# Resonator_filter_design.net
KiCad netlist of a schematic drawn in Altium Designer
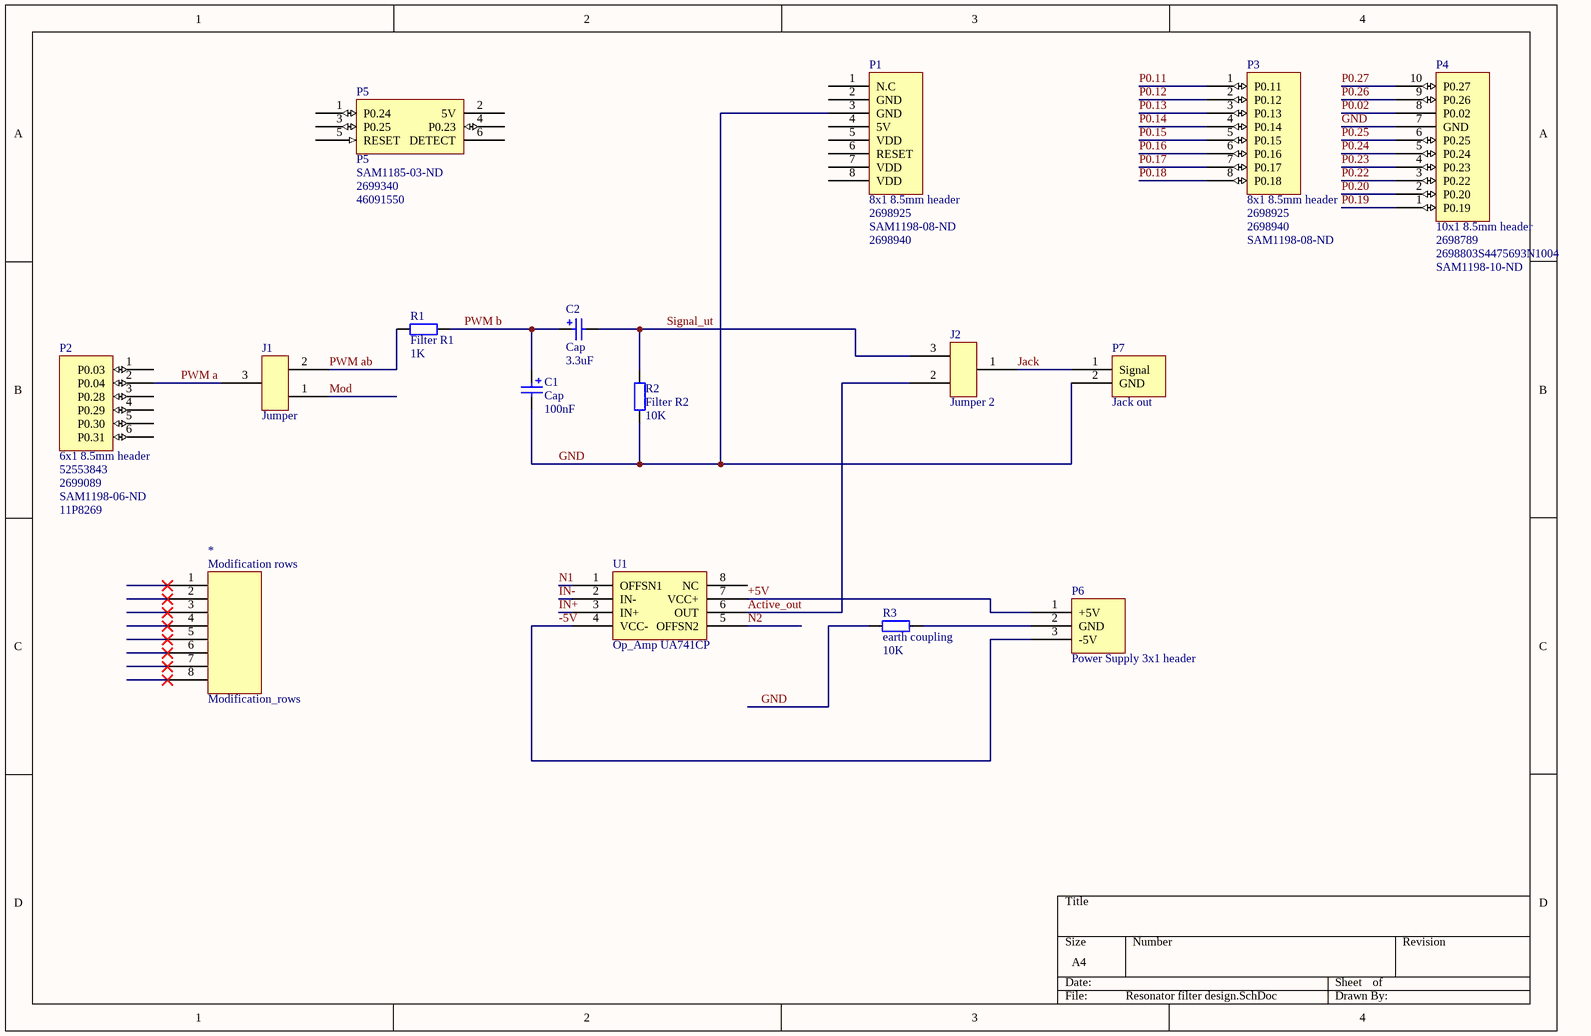
[diagram p0: Resonator filter design.SchDoc]

(export (version "E")
  (design (tool "Eeschema 10.0.6"))
  (components
    (comp (ref "*")
      (value "Modification_rows")
      (libsource (lib "Resonator filter design") (part "Modification_rows"))
    )
    (comp (ref "C1")
      (value "Cap")
      (footprint "Cap 100nF")
      (description "Polarized Capacitor (Axial)")
      (fields (field (name "ALTIUM_VALUE") "100nF") (field (name "PUBLISHER") "Altium Limited"))
      (libsource (lib "Miscellaneous Devices") (part "Cap Pol2"))
    )
    (comp (ref "C2")
      (value "Cap")
      (footprint "Cap 3.3uF")
      (description "Polarized Capacitor (Axial)")
      (fields (field (name "ALTIUM_VALUE") "3.3uF") (field (name "PUBLISHER") "Altium Limited"))
      (libsource (lib "Miscellaneous Devices") (part "Cap Pol2"))
    )
    (comp (ref "J1")
      (value "Jumper")
      (footprint "Jumper")
      (libsource (lib "Resonator filter design") (part "Jumper"))
    )
    (comp (ref "J2")
      (value "Jumper 2")
      (footprint "Jumper2")
      (libsource (lib "Resonator filter design") (part "Jumper 2"))
    )
    (comp (ref "P1")
      (value "8x1 8.5mm header")
      (footprint "Header 8x1 8.5mm")
      (fields
        (field (name "SUPPLIER PART NUMBER 1") "2698925")
        (field (name "SUPPLIER PART NUMBER 2") "SAM1198-08-ND")
        (field (name "SUPPLIER PART NUMBER 3") "2698940")
      )
      (libsource (lib "Resonator filter design") (part "POWER P1"))
    )
    (comp (ref "P2")
      (value "6x1 8.5mm header")
      (footprint "Header 6x1 8.5mm")
      (fields
        (field (name "SUPPLIER PART NUMBER 1") "52553843")
        (field (name "SUPPLIER PART NUMBER 2") "2699089")
        (field (name "SUPPLIER PART NUMBER 3") "SAM1198-06-ND")
        (field (name "SUPPLIER PART NUMBER 4") "11P8269")
      )
      (libsource (lib "Resonator filter design") (part "P2"))
    )
    (comp (ref "P3")
      (value "8x1 8.5mm header")
      (footprint "Header 8x1 8.5mm")
      (fields
        (field (name "SUPPLIER PART NUMBER 1") "2698925")
        (field (name "SUPPLIER PART NUMBER 2") "2698940")
        (field (name "SUPPLIER PART NUMBER 3") "SAM1198-08-ND")
      )
      (libsource (lib "Resonator filter design") (part "P3"))
    )
    (comp (ref "P4")
      (value "10x1 8.5mm header")
      (footprint "Header 10x1 8.5mm")
      (fields
        (field (name "SUPPLIER PART NUMBER 1") "2698789")
        (field (name "SUPPLIER PART NUMBER 2") "2698803S4475693N1004")
        (field (name "SUPPLIER PART NUMBER 3") "SAM1198-10-ND")
      )
      (libsource (lib "Resonator filter design") (part "P4"))
    )
    (comp (ref "P5")
      (value "P5")
      (footprint "ICSP")
      (fields
        (field (name "SUPPLIER PART NUMBER 1") "SAM1185-03-ND")
        (field (name "SUPPLIER PART NUMBER 2") "2699340")
        (field (name "SUPPLIER PART NUMBER 3") "46091550")
      )
      (libsource (lib "Resonator filter design") (part "P5"))
    )
    (comp (ref "P6")
      (value "Power Supply 3x1 header")
      (footprint "Power Supply connector")
      (libsource (lib "Resonator filter design") (part "Power Supply"))
    )
    (comp (ref "P7")
      (value "Jack out")
      (footprint "Jack out")
      (libsource (lib "Resonator filter design") (part "Jack out"))
    )
    (comp (ref "R1")
      (value "Filter R1")
      (footprint "AXIAL-0.4")
      (description "Resistor")
      (fields (field (name "ALTIUM_VALUE") "1K") (field (name "PUBLISHER") "Altium Limited"))
      (libsource (lib "") (part "Res2_2"))
    )
    (comp (ref "R2")
      (value "Filter R2")
      (footprint "AXIAL-0.4")
      (description "Resistor")
      (fields (field (name "ALTIUM_VALUE") "10K") (field (name "PUBLISHER") "Altium Limited"))
      (libsource (lib "") (part "Res2_1"))
    )
    (comp (ref "R3")
      (value "earth coupling")
      (footprint "AXIAL-0.4")
      (description "Resistor")
      (fields (field (name "ALTIUM_VALUE") "10K") (field (name "PUBLISHER") "Altium Limited"))
      (libsource (lib "Miscellaneous Devices") (part "Res2"))
    )
    (comp (ref "U1")
      (value "Op_Amp UA741CP")
      (footprint "Op-Amp UA741CP")
      (libsource (lib "Resonator filter design") (part "Op_Amp UA741CP"))
    )
  )
  (nets
    (net (code "1") (name "/+5V") (class "Default")
      (node (ref "P6") (pin "1") (pinfunction "+5V_1") (pintype "passive"))
      (node (ref "U1") (pin "7") (pinfunction "VCC+_7") (pintype "passive"))
    )
    (net (code "2") (name "/-5V") (class "Default")
      (node (ref "P6") (pin "3") (pinfunction "-5V_3") (pintype "passive"))
      (node (ref "U1") (pin "4") (pinfunction "VCC-_4") (pintype "passive"))
    )
    (net (code "3") (name "/Active_out") (class "Default")
      (node (ref "J2") (pin "2") (pintype "passive"))
      (node (ref "U1") (pin "6") (pinfunction "OUT_6") (pintype "passive"))
    )
    (net (code "4") (name "/GND") (class "Default")
      (node (ref "C1") (pin "2") (pinfunction "2_2") (pintype "passive"))
      (node (ref "P1") (pin "3") (pinfunction "GND_3") (pintype "power_in"))
      (node (ref "P4") (pin "7") (pinfunction "GND_7") (pintype "power_in"))
      (node (ref "P7") (pin "2") (pinfunction "GND_2") (pintype "passive"))
      (node (ref "R2") (pin "1") (pinfunction "1_1") (pintype "passive"))
      (node (ref "R3") (pin "2") (pinfunction "2_2") (pintype "passive"))
    )
    (net (code "5") (name "/IN+") (class "Default")
      (node (ref "U1") (pin "3") (pinfunction "IN+_3") (pintype "passive"))
    )
    (net (code "6") (name "/IN-") (class "Default")
      (node (ref "U1") (pin "2") (pinfunction "IN-_2") (pintype "passive"))
    )
    (net (code "7") (name "/Jack") (class "Default")
      (node (ref "J2") (pin "1") (pintype "passive"))
      (node (ref "P7") (pin "1") (pinfunction "Signal_1") (pintype "passive"))
    )
    (net (code "8") (name "/Mod") (class "Default") (node (ref "J1") (pin "1") (pintype "passive")))
    (net (code "9") (name "/N1") (class "Default")
      (node (ref "U1") (pin "1") (pinfunction "OFFSN1_1") (pintype "passive"))
    )
    (net (code "10") (name "/N2") (class "Default")
      (node (ref "U1") (pin "5") (pinfunction "OFFSN2_5") (pintype "passive"))
    )
    (net (code "11") (name "/P0.02") (class "Default")
      (node (ref "P4") (pin "8") (pinfunction "P0.02_8") (pintype "passive"))
    )
    (net (code "12") (name "/P0.11") (class "Default")
      (node (ref "P3") (pin "1") (pinfunction "P0.11_1") (pintype "bidirectional"))
    )
    (net (code "13") (name "/P0.12") (class "Default")
      (node (ref "P3") (pin "2") (pinfunction "P0.12_2") (pintype "bidirectional"))
    )
    (net (code "14") (name "/P0.13") (class "Default")
      (node (ref "P3") (pin "3") (pinfunction "P0.13_3") (pintype "bidirectional"))
    )
    (net (code "15") (name "/P0.14") (class "Default")
      (node (ref "P3") (pin "4") (pinfunction "P0.14_4") (pintype "bidirectional"))
    )
    (net (code "16") (name "/P0.15") (class "Default")
      (node (ref "P3") (pin "5") (pinfunction "P0.15_5") (pintype "bidirectional"))
    )
    (net (code "17") (name "/P0.16") (class "Default")
      (node (ref "P3") (pin "6") (pinfunction "P0.16_6") (pintype "bidirectional"))
    )
    (net (code "18") (name "/P0.17") (class "Default")
      (node (ref "P3") (pin "7") (pinfunction "P0.17_7") (pintype "bidirectional"))
    )
    (net (code "19") (name "/P0.18") (class "Default")
      (node (ref "P3") (pin "8") (pinfunction "P0.18_8") (pintype "bidirectional"))
    )
    (net (code "20") (name "/P0.19") (class "Default")
      (node (ref "P4") (pin "1") (pinfunction "P0.19_1") (pintype "bidirectional"))
    )
    (net (code "21") (name "/P0.20") (class "Default")
      (node (ref "P4") (pin "2") (pinfunction "P0.20_2") (pintype "bidirectional"))
    )
    (net (code "22") (name "/P0.22") (class "Default")
      (node (ref "P4") (pin "3") (pinfunction "P0.22_3") (pintype "bidirectional"))
    )
    (net (code "23") (name "/P0.23") (class "Default")
      (node (ref "P4") (pin "4") (pinfunction "P0.23_4") (pintype "bidirectional"))
    )
    (net (code "24") (name "/P0.24") (class "Default")
      (node (ref "P4") (pin "5") (pinfunction "P0.24_5") (pintype "bidirectional"))
    )
    (net (code "25") (name "/P0.25") (class "Default")
      (node (ref "P4") (pin "6") (pinfunction "P0.25_6") (pintype "bidirectional"))
    )
    (net (code "26") (name "/P0.26") (class "Default")
      (node (ref "P4") (pin "9") (pinfunction "P0.26_9") (pintype "bidirectional"))
    )
    (net (code "27") (name "/P0.27") (class "Default")
      (node (ref "P4") (pin "10") (pinfunction "P0.27_10") (pintype "bidirectional"))
    )
    (net (code "28") (name "/PWM a") (class "Default")
      (node (ref "J1") (pin "3") (pintype "passive"))
      (node (ref "P2") (pin "2") (pinfunction "P0.04_2") (pintype "bidirectional"))
    )
    (net (code "29") (name "/PWM ab") (class "Default")
      (node (ref "J1") (pin "2") (pintype "passive"))
      (node (ref "R1") (pin "1") (pinfunction "1_1") (pintype "passive"))
    )
    (net (code "30") (name "/PWM b") (class "Default")
      (node (ref "C1") (pin "1") (pinfunction "1_1") (pintype "passive"))
      (node (ref "C2") (pin "1") (pinfunction "1_1") (pintype "passive"))
      (node (ref "R1") (pin "2") (pinfunction "2_2") (pintype "passive"))
    )
    (net (code "31") (name "/Signal_ut") (class "Default")
      (node (ref "C2") (pin "2") (pinfunction "2_2") (pintype "passive"))
      (node (ref "J2") (pin "3") (pintype "passive"))
      (node (ref "R2") (pin "2") (pinfunction "2_2") (pintype "passive"))
    )
    (net (code "32") (name "Net-(P6-GND)") (class "Default")
      (node (ref "P6") (pin "2") (pinfunction "GND_2") (pintype "passive"))
      (node (ref "R3") (pin "1") (pinfunction "1_1") (pintype "passive"))
    )
    (net (code "33") (name "unconnected-(*-Pad1)") (class "Default")
      (node (ref "*") (pin "1") (pintype "passive+no_connect"))
    )
    (net (code "34") (name "unconnected-(*-Pad2)") (class "Default")
      (node (ref "*") (pin "2") (pintype "passive+no_connect"))
    )
    (net (code "35") (name "unconnected-(*-Pad3)") (class "Default")
      (node (ref "*") (pin "3") (pintype "passive+no_connect"))
    )
    (net (code "36") (name "unconnected-(*-Pad4)") (class "Default")
      (node (ref "*") (pin "4") (pintype "passive+no_connect"))
    )
    (net (code "37") (name "unconnected-(*-Pad5)") (class "Default")
      (node (ref "*") (pin "5") (pintype "passive+no_connect"))
    )
    (net (code "38") (name "unconnected-(*-Pad6)") (class "Default")
      (node (ref "*") (pin "6") (pintype "passive+no_connect"))
    )
    (net (code "39") (name "unconnected-(*-Pad7)") (class "Default")
      (node (ref "*") (pin "7") (pintype "passive+no_connect"))
    )
    (net (code "40") (name "unconnected-(*-Pad8)") (class "Default")
      (node (ref "*") (pin "8") (pintype "passive+no_connect"))
    )
    (net (code "41") (name "unconnected-(P1-5V-Pad4)") (class "Default")
      (node (ref "P1") (pin "4") (pinfunction "5V_4") (pintype "power_in"))
    )
    (net (code "42") (name "unconnected-(P1-GND-Pad2)") (class "Default")
      (node (ref "P1") (pin "2") (pinfunction "GND_2") (pintype "power_in"))
    )
    (net (code "43") (name "unconnected-(P1-N.C-Pad1)") (class "Default")
      (node (ref "P1") (pin "1") (pinfunction "N.C_1") (pintype "power_in"))
    )
    (net (code "44") (name "unconnected-(P1-RESET-Pad6)") (class "Default")
      (node (ref "P1") (pin "6") (pinfunction "RESET_6") (pintype "passive"))
    )
    (net (code "45") (name "unconnected-(P1-VDD-Pad5)") (class "Default")
      (node (ref "P1") (pin "5") (pinfunction "VDD_5") (pintype "power_in"))
    )
    (net (code "46") (name "unconnected-(P1-VDD-Pad7)") (class "Default")
      (node (ref "P1") (pin "7") (pinfunction "VDD_7") (pintype "power_in"))
    )
    (net (code "47") (name "unconnected-(P1-VDD-Pad8)") (class "Default")
      (node (ref "P1") (pin "8") (pinfunction "VDD_8") (pintype "passive"))
    )
    (net (code "48") (name "unconnected-(P2-P0.03-Pad1)") (class "Default")
      (node (ref "P2") (pin "1") (pinfunction "P0.03_1") (pintype "bidirectional"))
    )
    (net (code "49") (name "unconnected-(P2-P0.28-Pad3)") (class "Default")
      (node (ref "P2") (pin "3") (pinfunction "P0.28_3") (pintype "bidirectional"))
    )
    (net (code "50") (name "unconnected-(P2-P0.29-Pad4)") (class "Default")
      (node (ref "P2") (pin "4") (pinfunction "P0.29_4") (pintype "bidirectional"))
    )
    (net (code "51") (name "unconnected-(P2-P0.30-Pad5)") (class "Default")
      (node (ref "P2") (pin "5") (pinfunction "P0.30_5") (pintype "bidirectional"))
    )
    (net (code "52") (name "unconnected-(P2-P0.31-Pad6)") (class "Default")
      (node (ref "P2") (pin "6") (pinfunction "P0.31_6") (pintype "bidirectional"))
    )
    (net (code "53") (name "unconnected-(P5-5V-Pad2)") (class "Default")
      (node (ref "P5") (pin "2") (pinfunction "5V_2") (pintype "power_in"))
    )
    (net (code "54") (name "unconnected-(P5-DETECT-Pad6)") (class "Default")
      (node (ref "P5") (pin "6") (pinfunction "DETECT_6") (pintype "power_in"))
    )
    (net (code "55") (name "unconnected-(P5-P0.23-Pad4)") (class "Default")
      (node (ref "P5") (pin "4") (pinfunction "P0.23_4") (pintype "bidirectional"))
    )
    (net (code "56") (name "unconnected-(P5-P0.24-Pad1)") (class "Default")
      (node (ref "P5") (pin "1") (pinfunction "P0.24_1") (pintype "bidirectional"))
    )
    (net (code "57") (name "unconnected-(P5-P0.25-Pad3)") (class "Default")
      (node (ref "P5") (pin "3") (pinfunction "P0.25_3") (pintype "bidirectional"))
    )
    (net (code "58") (name "unconnected-(P5-RESET-Pad5)") (class "Default")
      (node (ref "P5") (pin "5") (pinfunction "RESET_5") (pintype "input"))
    )
    (net (code "59") (name "unconnected-(U1-NC-Pad8)") (class "Default")
      (node (ref "U1") (pin "8") (pinfunction "NC_8") (pintype "passive"))
    )
  )
)
